# Energy-Monitor-FeatherWing-ATSAMD21.net
KiCad netlist of a schematic drawn in EAGLE
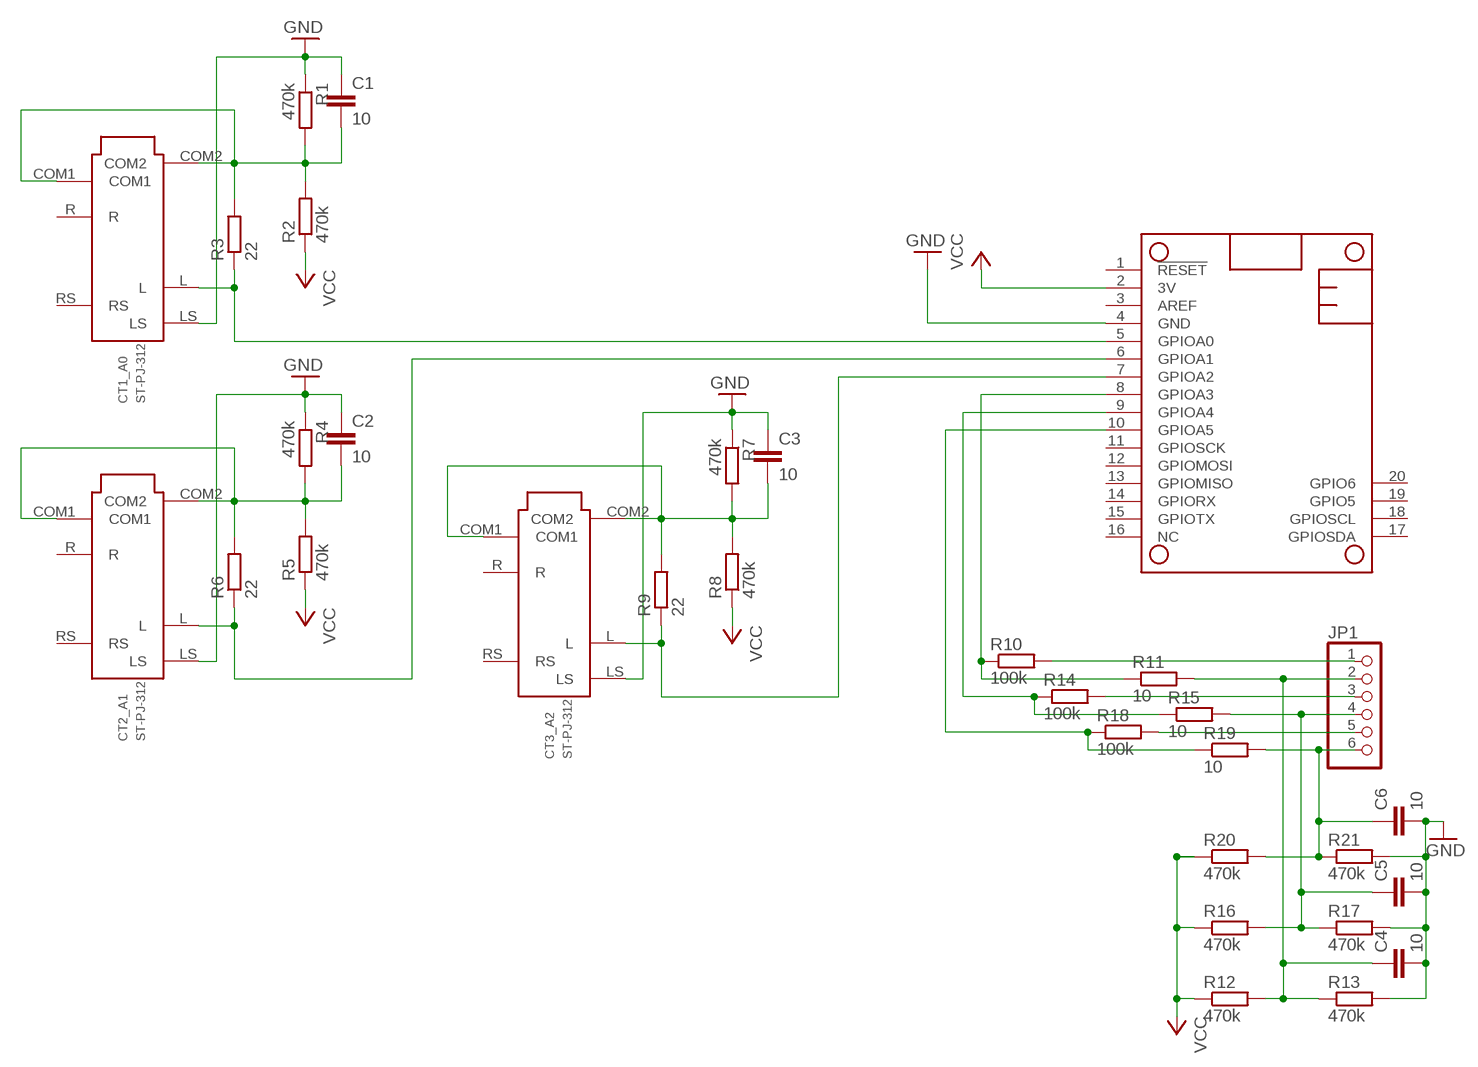
[diagram p0: schematic, sheet 1]

(export (version "E")
  (design (tool "Eeschema 10.0.6"))
  (components
    (comp (ref "C1")
      (value "10")
      (footprint "eagle-import:C0402")
      (libsource (lib "eagle-import") (part "C-EUC0402"))
    )
    (comp (ref "C2")
      (value "10")
      (footprint "eagle-import:C0402")
      (libsource (lib "eagle-import") (part "C-EUC0402"))
    )
    (comp (ref "C3")
      (value "10")
      (footprint "eagle-import:C0402")
      (libsource (lib "eagle-import") (part "C-EUC0402"))
    )
    (comp (ref "C4")
      (value "10")
      (footprint "eagle-import:C0402")
      (libsource (lib "eagle-import") (part "C-EUC0402"))
    )
    (comp (ref "C5")
      (value "10")
      (footprint "eagle-import:C0402")
      (libsource (lib "eagle-import") (part "C-EUC0402"))
    )
    (comp (ref "C6")
      (value "10")
      (footprint "eagle-import:C0402")
      (libsource (lib "eagle-import") (part "C-EUC0402"))
    )
    (comp (ref "CT1_A0")
      (value "ST-PJ-312")
      (footprint "eagle-import:SUNTECH_ST-PJ-312")
      (libsource (lib "eagle-import") (part "ST-PJ-312"))
    )
    (comp (ref "CT2_A1")
      (value "ST-PJ-312")
      (footprint "eagle-import:SUNTECH_ST-PJ-312")
      (libsource (lib "eagle-import") (part "ST-PJ-312"))
    )
    (comp (ref "CT3_A2")
      (value "ST-PJ-312")
      (footprint "eagle-import:SUNTECH_ST-PJ-312")
      (libsource (lib "eagle-import") (part "ST-PJ-312"))
    )
    (comp (ref "JP1")
      (value "PINHD-1X6CB")
      (footprint "eagle-import:1X06-CLEANBIG")
      (libsource (lib "eagle-import") (part "PINHD-1X6CB"))
    )
    (comp (ref "MS1")
      (value "FEATHERWING")
      (footprint "eagle-import:FEATHERWING")
      (libsource (lib "eagle-import") (part "FEATHERWING"))
    )
    (comp (ref "R1")
      (value "470k")
      (footprint "eagle-import:R0402")
      (libsource (lib "eagle-import") (part "R-EU_R0402"))
    )
    (comp (ref "R2")
      (value "470k")
      (footprint "eagle-import:R0402")
      (libsource (lib "eagle-import") (part "R-EU_R0402"))
    )
    (comp (ref "R3")
      (value "22")
      (footprint "eagle-import:R0402")
      (libsource (lib "eagle-import") (part "R-EU_R0402"))
    )
    (comp (ref "R4")
      (value "470k")
      (footprint "eagle-import:R0402")
      (libsource (lib "eagle-import") (part "R-EU_R0402"))
    )
    (comp (ref "R5")
      (value "470k")
      (footprint "eagle-import:R0402")
      (libsource (lib "eagle-import") (part "R-EU_R0402"))
    )
    (comp (ref "R6")
      (value "22")
      (footprint "eagle-import:R0402")
      (libsource (lib "eagle-import") (part "R-EU_R0402"))
    )
    (comp (ref "R7")
      (value "470k")
      (footprint "eagle-import:R0402")
      (libsource (lib "eagle-import") (part "R-EU_R0402"))
    )
    (comp (ref "R8")
      (value "470k")
      (footprint "eagle-import:R0402")
      (libsource (lib "eagle-import") (part "R-EU_R0402"))
    )
    (comp (ref "R9")
      (value "22")
      (footprint "eagle-import:R0402")
      (libsource (lib "eagle-import") (part "R-EU_R0402"))
    )
    (comp (ref "R10")
      (value "100k")
      (footprint "eagle-import:R0402")
      (libsource (lib "eagle-import") (part "R-EU_R0402"))
    )
    (comp (ref "R11")
      (value "10")
      (footprint "eagle-import:R0402")
      (libsource (lib "eagle-import") (part "R-EU_R0402"))
    )
    (comp (ref "R12")
      (value "470k")
      (footprint "eagle-import:R0402")
      (libsource (lib "eagle-import") (part "R-EU_R0402"))
    )
    (comp (ref "R13")
      (value "470k")
      (footprint "eagle-import:R0402")
      (libsource (lib "eagle-import") (part "R-EU_R0402"))
    )
    (comp (ref "R14")
      (value "100k")
      (footprint "eagle-import:R0402")
      (libsource (lib "eagle-import") (part "R-EU_R0402"))
    )
    (comp (ref "R15")
      (value "10")
      (footprint "eagle-import:R0402")
      (libsource (lib "eagle-import") (part "R-EU_R0402"))
    )
    (comp (ref "R16")
      (value "470k")
      (footprint "eagle-import:R0402")
      (libsource (lib "eagle-import") (part "R-EU_R0402"))
    )
    (comp (ref "R17")
      (value "470k")
      (footprint "eagle-import:R0402")
      (libsource (lib "eagle-import") (part "R-EU_R0402"))
    )
    (comp (ref "R18")
      (value "100k")
      (footprint "eagle-import:R0402")
      (libsource (lib "eagle-import") (part "R-EU_R0402"))
    )
    (comp (ref "R19")
      (value "10")
      (footprint "eagle-import:R0402")
      (libsource (lib "eagle-import") (part "R-EU_R0402"))
    )
    (comp (ref "R20")
      (value "470k")
      (footprint "eagle-import:R0402")
      (libsource (lib "eagle-import") (part "R-EU_R0402"))
    )
    (comp (ref "R21")
      (value "470k")
      (footprint "eagle-import:R0402")
      (libsource (lib "eagle-import") (part "R-EU_R0402"))
    )
  )
  (nets
    (net (code "1") (name "GND") (class "Default")
      (node (ref "C1") (pin "1") (pinfunction "1_1") (pintype "passive"))
      (node (ref "C2") (pin "1") (pinfunction "1_1") (pintype "passive"))
      (node (ref "C3") (pin "1") (pinfunction "1_1") (pintype "passive"))
      (node (ref "C4") (pin "2") (pinfunction "2_2") (pintype "passive"))
      (node (ref "C5") (pin "2") (pinfunction "2_2") (pintype "passive"))
      (node (ref "C6") (pin "2") (pinfunction "2_2") (pintype "passive"))
      (node (ref "CT1_A0") (pin "LS") (pinfunction "LS_LS") (pintype "bidirectional"))
      (node (ref "CT2_A1") (pin "LS") (pinfunction "LS_LS") (pintype "bidirectional"))
      (node (ref "CT3_A2") (pin "LS") (pinfunction "LS_LS") (pintype "bidirectional"))
      (node (ref "MS1") (pin "4") (pinfunction "GND_4") (pintype "power_in"))
      (node (ref "R1") (pin "1") (pinfunction "1_1") (pintype "passive"))
      (node (ref "R13") (pin "2") (pinfunction "2_2") (pintype "passive"))
      (node (ref "R17") (pin "2") (pinfunction "2_2") (pintype "passive"))
      (node (ref "R21") (pin "2") (pinfunction "2_2") (pintype "passive"))
      (node (ref "R4") (pin "1") (pinfunction "1_1") (pintype "passive"))
      (node (ref "R7") (pin "1") (pinfunction "1_1") (pintype "passive"))
    )
    (net (code "2") (name "Net-(C1-Pad2)") (class "Default")
      (node (ref "C1") (pin "2") (pinfunction "2_2") (pintype "passive"))
      (node (ref "CT1_A0") (pin "COM1") (pinfunction "COM1_COM1") (pintype "bidirectional"))
      (node (ref "CT1_A0") (pin "COM2") (pinfunction "COM2_COM2") (pintype "bidirectional"))
      (node (ref "R1") (pin "2") (pinfunction "2_2") (pintype "passive"))
      (node (ref "R2") (pin "2") (pinfunction "2_2") (pintype "passive"))
      (node (ref "R3") (pin "2") (pinfunction "2_2") (pintype "passive"))
    )
    (net (code "3") (name "Net-(C2-Pad2)") (class "Default")
      (node (ref "C2") (pin "2") (pinfunction "2_2") (pintype "passive"))
      (node (ref "CT2_A1") (pin "COM1") (pinfunction "COM1_COM1") (pintype "bidirectional"))
      (node (ref "CT2_A1") (pin "COM2") (pinfunction "COM2_COM2") (pintype "bidirectional"))
      (node (ref "R4") (pin "2") (pinfunction "2_2") (pintype "passive"))
      (node (ref "R5") (pin "2") (pinfunction "2_2") (pintype "passive"))
      (node (ref "R6") (pin "2") (pinfunction "2_2") (pintype "passive"))
    )
    (net (code "4") (name "Net-(C3-Pad2)") (class "Default")
      (node (ref "C3") (pin "2") (pinfunction "2_2") (pintype "passive"))
      (node (ref "CT3_A2") (pin "COM1") (pinfunction "COM1_COM1") (pintype "bidirectional"))
      (node (ref "CT3_A2") (pin "COM2") (pinfunction "COM2_COM2") (pintype "bidirectional"))
      (node (ref "R7") (pin "2") (pinfunction "2_2") (pintype "passive"))
      (node (ref "R8") (pin "2") (pinfunction "2_2") (pintype "passive"))
      (node (ref "R9") (pin "2") (pinfunction "2_2") (pintype "passive"))
    )
    (net (code "5") (name "Net-(C4-Pad1)") (class "Default")
      (node (ref "C4") (pin "1") (pinfunction "1_1") (pintype "passive"))
      (node (ref "JP1") (pin "2") (pinfunction "2_2") (pintype "passive"))
      (node (ref "R11") (pin "2") (pinfunction "2_2") (pintype "passive"))
      (node (ref "R12") (pin "2") (pinfunction "2_2") (pintype "passive"))
      (node (ref "R13") (pin "1") (pinfunction "1_1") (pintype "passive"))
    )
    (net (code "6") (name "Net-(C5-Pad1)") (class "Default")
      (node (ref "C5") (pin "1") (pinfunction "1_1") (pintype "passive"))
      (node (ref "JP1") (pin "4") (pinfunction "4_4") (pintype "passive"))
      (node (ref "R15") (pin "2") (pinfunction "2_2") (pintype "passive"))
      (node (ref "R16") (pin "2") (pinfunction "2_2") (pintype "passive"))
      (node (ref "R17") (pin "1") (pinfunction "1_1") (pintype "passive"))
    )
    (net (code "7") (name "Net-(C6-Pad1)") (class "Default")
      (node (ref "C6") (pin "1") (pinfunction "1_1") (pintype "passive"))
      (node (ref "JP1") (pin "6") (pinfunction "6_6") (pintype "passive"))
      (node (ref "R19") (pin "2") (pinfunction "2_2") (pintype "passive"))
      (node (ref "R20") (pin "2") (pinfunction "2_2") (pintype "passive"))
      (node (ref "R21") (pin "1") (pinfunction "1_1") (pintype "passive"))
    )
    (net (code "8") (name "Net-(JP1-Pad1)") (class "Default")
      (node (ref "JP1") (pin "1") (pinfunction "1_1") (pintype "passive"))
      (node (ref "R10") (pin "2") (pinfunction "2_2") (pintype "passive"))
    )
    (net (code "9") (name "Net-(JP1-Pad3)") (class "Default")
      (node (ref "JP1") (pin "3") (pinfunction "3_3") (pintype "passive"))
      (node (ref "R14") (pin "2") (pinfunction "2_2") (pintype "passive"))
    )
    (net (code "10") (name "Net-(JP1-Pad5)") (class "Default")
      (node (ref "JP1") (pin "5") (pinfunction "5_5") (pintype "passive"))
      (node (ref "R18") (pin "2") (pinfunction "2_2") (pintype "passive"))
    )
    (net (code "11") (name "Net-(MS1-GPIOA0)") (class "Default")
      (node (ref "CT1_A0") (pin "L") (pinfunction "L_L") (pintype "bidirectional"))
      (node (ref "MS1") (pin "5") (pinfunction "GPIOA0_5") (pintype "bidirectional"))
      (node (ref "R3") (pin "1") (pinfunction "1_1") (pintype "passive"))
    )
    (net (code "12") (name "Net-(MS1-GPIOA1)") (class "Default")
      (node (ref "CT2_A1") (pin "L") (pinfunction "L_L") (pintype "bidirectional"))
      (node (ref "MS1") (pin "6") (pinfunction "GPIOA1_6") (pintype "bidirectional"))
      (node (ref "R6") (pin "1") (pinfunction "1_1") (pintype "passive"))
    )
    (net (code "13") (name "Net-(MS1-GPIOA2)") (class "Default")
      (node (ref "CT3_A2") (pin "L") (pinfunction "L_L") (pintype "bidirectional"))
      (node (ref "MS1") (pin "7") (pinfunction "GPIOA2_7") (pintype "bidirectional"))
      (node (ref "R9") (pin "1") (pinfunction "1_1") (pintype "passive"))
    )
    (net (code "14") (name "Net-(MS1-GPIOA3)") (class "Default")
      (node (ref "MS1") (pin "8") (pinfunction "GPIOA3_8") (pintype "bidirectional"))
      (node (ref "R10") (pin "1") (pinfunction "1_1") (pintype "passive"))
      (node (ref "R11") (pin "1") (pinfunction "1_1") (pintype "passive"))
    )
    (net (code "15") (name "Net-(MS1-GPIOA4)") (class "Default")
      (node (ref "MS1") (pin "9") (pinfunction "GPIOA4_9") (pintype "bidirectional"))
      (node (ref "R14") (pin "1") (pinfunction "1_1") (pintype "passive"))
      (node (ref "R15") (pin "1") (pinfunction "1_1") (pintype "passive"))
    )
    (net (code "16") (name "Net-(MS1-GPIOA5)") (class "Default")
      (node (ref "MS1") (pin "10") (pinfunction "GPIOA5_10") (pintype "bidirectional"))
      (node (ref "R18") (pin "1") (pinfunction "1_1") (pintype "passive"))
      (node (ref "R19") (pin "1") (pinfunction "1_1") (pintype "passive"))
    )
    (net (code "17") (name "VCC") (class "Default")
      (node (ref "MS1") (pin "2") (pinfunction "3V_2") (pintype "power_in"))
      (node (ref "R12") (pin "1") (pinfunction "1_1") (pintype "passive"))
      (node (ref "R16") (pin "1") (pinfunction "1_1") (pintype "passive"))
      (node (ref "R2") (pin "1") (pinfunction "1_1") (pintype "passive"))
      (node (ref "R20") (pin "1") (pinfunction "1_1") (pintype "passive"))
      (node (ref "R5") (pin "1") (pinfunction "1_1") (pintype "passive"))
      (node (ref "R8") (pin "1") (pinfunction "1_1") (pintype "passive"))
    )
    (net (code "18") (name "unconnected-(CT1_A0-PadR)") (class "Default")
      (node (ref "CT1_A0") (pin "R") (pinfunction "R_R") (pintype "bidirectional"))
    )
    (net (code "19") (name "unconnected-(CT1_A0-PadRS)") (class "Default")
      (node (ref "CT1_A0") (pin "RS") (pinfunction "RS_RS") (pintype "bidirectional"))
    )
    (net (code "20") (name "unconnected-(CT2_A1-PadR)") (class "Default")
      (node (ref "CT2_A1") (pin "R") (pinfunction "R_R") (pintype "bidirectional"))
    )
    (net (code "21") (name "unconnected-(CT2_A1-PadRS)") (class "Default")
      (node (ref "CT2_A1") (pin "RS") (pinfunction "RS_RS") (pintype "bidirectional"))
    )
    (net (code "22") (name "unconnected-(CT3_A2-PadR)") (class "Default")
      (node (ref "CT3_A2") (pin "R") (pinfunction "R_R") (pintype "bidirectional"))
    )
    (net (code "23") (name "unconnected-(CT3_A2-PadRS)") (class "Default")
      (node (ref "CT3_A2") (pin "RS") (pinfunction "RS_RS") (pintype "bidirectional"))
    )
    (net (code "24") (name "unconnected-(MS1-AREF-Pad3)") (class "Default")
      (node (ref "MS1") (pin "3") (pinfunction "AREF_3") (pintype "passive"))
    )
    (net (code "25") (name "unconnected-(MS1-GPIO5-Pad19)") (class "Default")
      (node (ref "MS1") (pin "19") (pinfunction "GPIO5_19") (pintype "bidirectional"))
    )
    (net (code "26") (name "unconnected-(MS1-GPIO6-Pad20)") (class "Default")
      (node (ref "MS1") (pin "20") (pinfunction "GPIO6_20") (pintype "bidirectional"))
    )
    (net (code "27") (name "unconnected-(MS1-GPIOMISO-Pad13)") (class "Default")
      (node (ref "MS1") (pin "13") (pinfunction "GPIOMISO_13") (pintype "bidirectional"))
    )
    (net (code "28") (name "unconnected-(MS1-GPIOMOSI-Pad12)") (class "Default")
      (node (ref "MS1") (pin "12") (pinfunction "GPIOMOSI_12") (pintype "bidirectional"))
    )
    (net (code "29") (name "unconnected-(MS1-GPIORX-Pad14)") (class "Default")
      (node (ref "MS1") (pin "14") (pinfunction "GPIORX_14") (pintype "bidirectional"))
    )
    (net (code "30") (name "unconnected-(MS1-GPIOSCK-Pad11)") (class "Default")
      (node (ref "MS1") (pin "11") (pinfunction "GPIOSCK_11") (pintype "bidirectional"))
    )
    (net (code "31") (name "unconnected-(MS1-GPIOSCL-Pad18)") (class "Default")
      (node (ref "MS1") (pin "18") (pinfunction "GPIOSCL_18") (pintype "bidirectional"))
    )
    (net (code "32") (name "unconnected-(MS1-GPIOSDA-Pad17)") (class "Default")
      (node (ref "MS1") (pin "17") (pinfunction "GPIOSDA_17") (pintype "bidirectional"))
    )
    (net (code "33") (name "unconnected-(MS1-GPIOTX-Pad15)") (class "Default")
      (node (ref "MS1") (pin "15") (pinfunction "GPIOTX_15") (pintype "bidirectional"))
    )
    (net (code "34") (name "unconnected-(MS1-NC-Pad16)") (class "Default")
      (node (ref "MS1") (pin "16") (pinfunction "NC_16") (pintype "passive"))
    )
    (net (code "35") (name "unconnected-(MS1-~{RESET}-Pad1)") (class "Default")
      (node (ref "MS1") (pin "1") (pinfunction "~{RESET}_1") (pintype "input"))
    )
  )
)
